# GPSLoRaNode_Schematic.net
KiCad netlist of a schematic drawn in Altium Designer
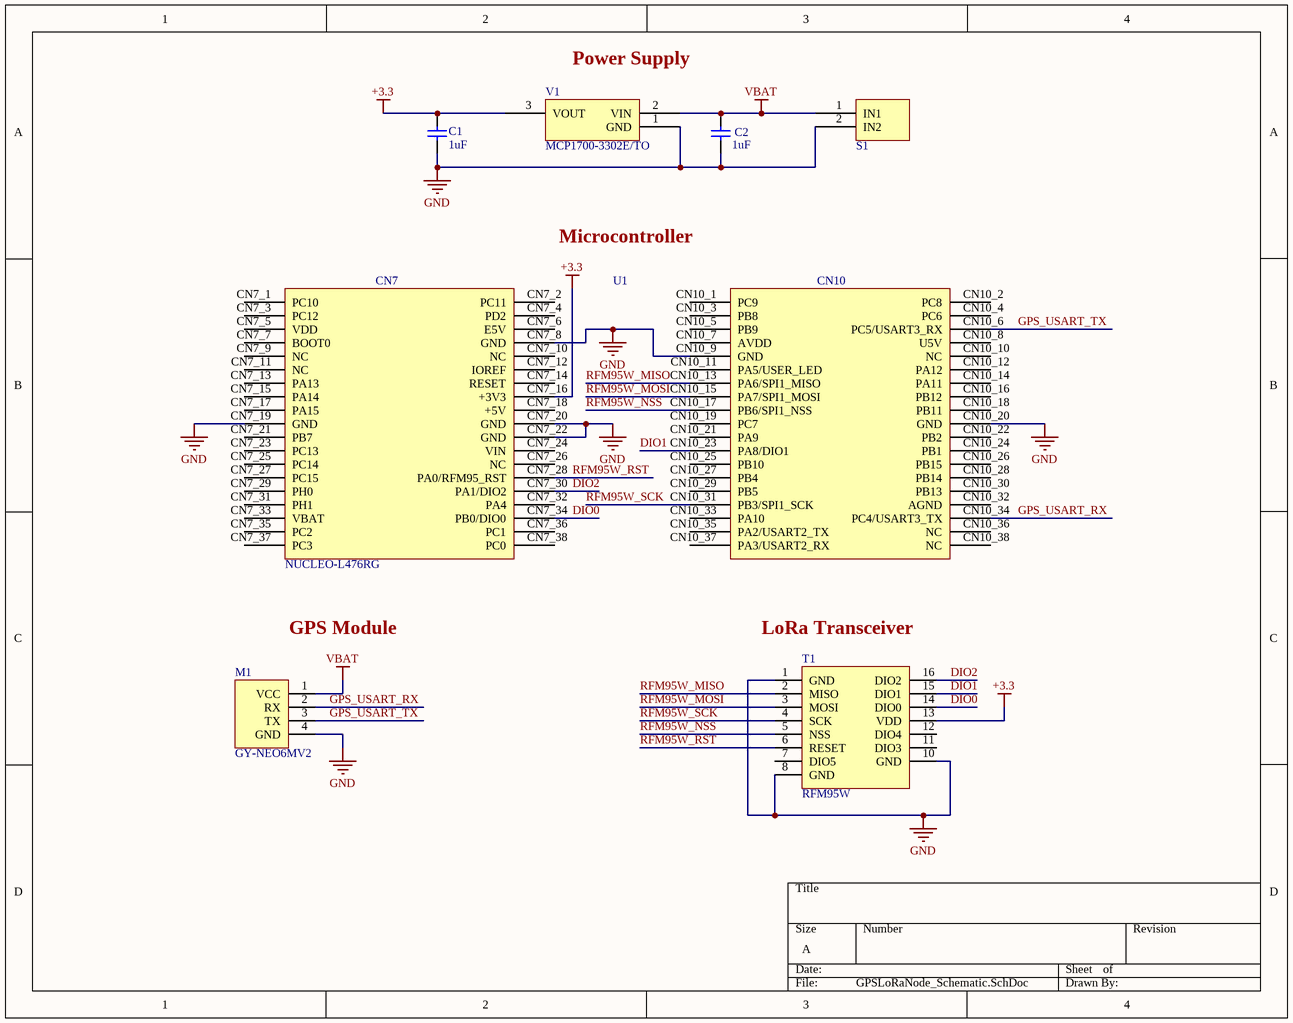
[diagram p0: GPSLoRaNode_Schematic.SchDoc]

(export (version "E")
  (design (tool "Eeschema 10.0.6"))
  (components
    (comp (ref "C1")
      (value "1uF")
      (footprint "C1uFTantalum")
      (description "CAP TANT 1UF 10% 35V RADIAL")
      (fields
        (field (name "MANUFACTURER") "KEMET")
        (field (name "MANUFACTURER PART NUMBER") "T350A105K035AS7301")
      )
      (libsource (lib "GPSLoRaNode") (part "T350A105K035AS7301"))
    )
    (comp (ref "C2")
      (value "1uF")
      (footprint "C1uFTantalum")
      (description "CAP TANT 1UF 10% 35V RADIAL")
      (fields
        (field (name "MANUFACTURER") "KEMET")
        (field (name "MANUFACTURER PART NUMBER") "T350A105K035AS7301")
      )
      (libsource (lib "GPSLoRaNode") (part "T350A105K035AS7301"))
    )
    (comp (ref "M1") (value "GY-NEO6MV2") (libsource (lib "GPSLoRaNode") (part "GY-NEO6MV2")))
    (comp (ref "S1")
      (value "2PositionScrewTerminal")
      (footprint "2POSITIONSCREWTERMINAL")
      (fields
        (field (name "MANUFACTURER") "Phoenix Contact")
        (field (name "MANUFACTURER PART NUMBER") "1725656")
        (field (name "VOLTAGE") "125V")
      )
      (libsource (lib "GPSLoRaNode") (part "2PositionScrewTerminal"))
    )
    (comp (ref "T1")
      (value "RFM95W")
      (footprint "HDR1X8")
      (description "RFM95W Breakout Board")
      (fields (field (name "MANUFACTURER") "Molex") (field (name "MANUFACTURER PART NUMBER") "22-10-2061"))
      (libsource (lib "GPSLoRaNode") (part "RFM95W"))
    )
    (comp (ref "U1")
      (value "NUCLEO-L476RG")
      (footprint "NUCLEOL476RG")
      (description "16/32-BITS MICROS")
      (fields (field (name "MANUFACTURER") "STMicroelectronics"))
      (libsource (lib "GPSLoRaNode") (part "NUCLEO-L476RG"))
    )
    (comp (ref "V1")
      (value "MCP1700-3302E/TO")
      (footprint "MCP1700")
      (description "LDO Regulator Pos 3.3V 0.25A 3-Pin TO-92 Bag")
      (fields (field (name "MANUFACTURER") "Microchip"))
      (libsource (lib "GPSLoRaNode") (part "MCP1700-3302E/TO"))
    )
  )
  (nets
    (net (code "1") (name "+3.3") (class "Default")
      (node (ref "C1") (pin "2") (pinfunction "2_2") (pintype "passive"))
      (node (ref "T1") (pin "13") (pinfunction "VDD_13") (pintype "passive"))
      (node (ref "U1") (pin "CN7_16") (pinfunction "+3V3_CN7_16") (pintype "passive"))
      (node (ref "V1") (pin "3") (pinfunction "VOUT_3") (pintype "passive"))
    )
    (net (code "2") (name "/DIO0") (class "Default")
      (node (ref "T1") (pin "14") (pinfunction "DIO0_14") (pintype "passive"))
      (node (ref "U1") (pin "CN7_34") (pinfunction "PB0/DIO0_CN7_34") (pintype "passive"))
    )
    (net (code "3") (name "/DIO1") (class "Default")
      (node (ref "T1") (pin "15") (pinfunction "DIO1_15") (pintype "passive"))
      (node (ref "U1") (pin "CN10_23") (pinfunction "PA8/DIO1_CN10_23") (pintype "passive"))
    )
    (net (code "4") (name "/DIO2") (class "Default")
      (node (ref "T1") (pin "16") (pinfunction "DIO2_16") (pintype "passive"))
      (node (ref "U1") (pin "CN7_30") (pinfunction "PA1/DIO2_CN7_30") (pintype "passive"))
    )
    (net (code "5") (name "/GPS_USART_RX") (class "Default")
      (node (ref "M1") (pin "2") (pinfunction "RX_2") (pintype "passive"))
      (node (ref "U1") (pin "CN10_34") (pinfunction "PC4/USART3_TX_CN10_34") (pintype "passive"))
    )
    (net (code "6") (name "/GPS_USART_TX") (class "Default")
      (node (ref "M1") (pin "3") (pinfunction "TX_3") (pintype "passive"))
      (node (ref "U1") (pin "CN10_6") (pinfunction "PC5/USART3_RX_CN10_6") (pintype "passive"))
    )
    (net (code "7") (name "/RFM95W_MISO") (class "Default")
      (node (ref "T1") (pin "2") (pinfunction "MISO_2") (pintype "passive"))
      (node (ref "U1") (pin "CN10_13") (pinfunction "PA6/SPI1_MISO_CN10_13") (pintype "passive"))
    )
    (net (code "8") (name "/RFM95W_MOSI") (class "Default")
      (node (ref "T1") (pin "3") (pinfunction "MOSI_3") (pintype "passive"))
      (node (ref "U1") (pin "CN10_15") (pinfunction "PA7/SPI1_MOSI_CN10_15") (pintype "passive"))
    )
    (net (code "9") (name "/RFM95W_NSS") (class "Default")
      (node (ref "T1") (pin "5") (pinfunction "NSS_5") (pintype "passive"))
      (node (ref "U1") (pin "CN10_17") (pinfunction "PB6/SPI1_NSS_CN10_17") (pintype "passive"))
    )
    (net (code "10") (name "/RFM95W_RST") (class "Default")
      (node (ref "T1") (pin "6") (pinfunction "RESET_6") (pintype "passive"))
      (node (ref "U1") (pin "CN7_28") (pinfunction "PA0/RFM95_RST_CN7_28") (pintype "passive"))
    )
    (net (code "11") (name "/RFM95W_SCK") (class "Default")
      (node (ref "T1") (pin "4") (pinfunction "SCK_4") (pintype "passive"))
      (node (ref "U1") (pin "CN10_31") (pinfunction "PB3/SPI1_SCK_CN10_31") (pintype "passive"))
    )
    (net (code "12") (name "GND") (class "Default")
      (node (ref "C1") (pin "1") (pinfunction "1_1") (pintype "passive"))
      (node (ref "C2") (pin "1") (pinfunction "1_1") (pintype "passive"))
      (node (ref "M1") (pin "4") (pinfunction "GND_4") (pintype "passive"))
      (node (ref "S1") (pin "2") (pinfunction "IN2_2") (pintype "passive"))
      (node (ref "T1") (pin "1") (pinfunction "GND_1") (pintype "passive"))
      (node (ref "T1") (pin "10") (pinfunction "GND_10") (pintype "passive"))
      (node (ref "T1") (pin "8") (pinfunction "GND_8") (pintype "passive"))
      (node (ref "U1") (pin "CN10_20") (pinfunction "GND_CN10_20") (pintype "passive"))
      (node (ref "U1") (pin "CN10_9") (pinfunction "GND_CN10_9") (pintype "passive"))
      (node (ref "U1") (pin "CN7_19") (pinfunction "GND_CN7_19") (pintype "passive"))
      (node (ref "U1") (pin "CN7_20") (pinfunction "GND_CN7_20") (pintype "passive"))
      (node (ref "U1") (pin "CN7_22") (pinfunction "GND_CN7_22") (pintype "passive"))
      (node (ref "U1") (pin "CN7_8") (pinfunction "GND_CN7_8") (pintype "passive"))
      (node (ref "V1") (pin "1") (pinfunction "GND_1") (pintype "passive"))
    )
    (net (code "13") (name "VBAT") (class "Default")
      (node (ref "C2") (pin "2") (pinfunction "2_2") (pintype "passive"))
      (node (ref "M1") (pin "1") (pinfunction "VCC_1") (pintype "passive"))
      (node (ref "S1") (pin "1") (pinfunction "IN1_1") (pintype "passive"))
      (node (ref "V1") (pin "2") (pinfunction "VIN_2") (pintype "passive"))
    )
    (net (code "14") (name "unconnected-(T1-DIO3-Pad11)") (class "Default")
      (node (ref "T1") (pin "11") (pinfunction "DIO3_11") (pintype "passive"))
    )
    (net (code "15") (name "unconnected-(T1-DIO4-Pad12)") (class "Default")
      (node (ref "T1") (pin "12") (pinfunction "DIO4_12") (pintype "passive"))
    )
    (net (code "16") (name "unconnected-(T1-DIO5-Pad7)") (class "Default")
      (node (ref "T1") (pin "7") (pinfunction "DIO5_7") (pintype "passive"))
    )
    (net (code "17") (name "unconnected-(U1-+5V-PadCN7_18)") (class "Default")
      (node (ref "U1") (pin "CN7_18") (pinfunction "+5V_CN7_18") (pintype "passive"))
    )
    (net (code "18") (name "unconnected-(U1-AGND-PadCN10_32)") (class "Default")
      (node (ref "U1") (pin "CN10_32") (pinfunction "AGND_CN10_32") (pintype "passive"))
    )
    (net (code "19") (name "unconnected-(U1-AVDD-PadCN10_7)") (class "Default")
      (node (ref "U1") (pin "CN10_7") (pinfunction "AVDD_CN10_7") (pintype "passive"))
    )
    (net (code "20") (name "unconnected-(U1-BOOT0-PadCN7_7)") (class "Default")
      (node (ref "U1") (pin "CN7_7") (pinfunction "BOOT0_CN7_7") (pintype "passive"))
    )
    (net (code "21") (name "unconnected-(U1-E5V-PadCN7_6)") (class "Default")
      (node (ref "U1") (pin "CN7_6") (pinfunction "E5V_CN7_6") (pintype "passive"))
    )
    (net (code "22") (name "unconnected-(U1-IOREF-PadCN7_12)") (class "Default")
      (node (ref "U1") (pin "CN7_12") (pinfunction "IOREF_CN7_12") (pintype "passive"))
    )
    (net (code "23") (name "unconnected-(U1-NC-PadCN7_9)") (class "Default")
      (node (ref "U1") (pin "CN7_9") (pinfunction "NC_CN7_9") (pintype "passive"))
    )
    (net (code "24") (name "unconnected-(U1-NC-PadCN7_10)") (class "Default")
      (node (ref "U1") (pin "CN7_10") (pinfunction "NC_CN7_10") (pintype "passive"))
    )
    (net (code "25") (name "unconnected-(U1-NC-PadCN7_11)") (class "Default")
      (node (ref "U1") (pin "CN7_11") (pinfunction "NC_CN7_11") (pintype "passive"))
    )
    (net (code "26") (name "unconnected-(U1-NC-PadCN7_26)") (class "Default")
      (node (ref "U1") (pin "CN7_26") (pinfunction "NC_CN7_26") (pintype "passive"))
    )
    (net (code "27") (name "unconnected-(U1-NC-PadCN10_10)") (class "Default")
      (node (ref "U1") (pin "CN10_10") (pinfunction "NC_CN10_10") (pintype "passive"))
    )
    (net (code "28") (name "unconnected-(U1-NC-PadCN10_36)") (class "Default")
      (node (ref "U1") (pin "CN10_36") (pinfunction "NC_CN10_36") (pintype "passive"))
    )
    (net (code "29") (name "unconnected-(U1-NC-PadCN10_38)") (class "Default")
      (node (ref "U1") (pin "CN10_38") (pinfunction "NC_CN10_38") (pintype "passive"))
    )
    (net (code "30") (name "unconnected-(U1-PA2{slash}USART2_TX-PadCN10_35)") (class "Default")
      (node (ref "U1") (pin "CN10_35") (pinfunction "PA2/USART2_TX_CN10_35") (pintype "passive"))
    )
    (net (code "31") (name "unconnected-(U1-PA3{slash}USART2_RX-PadCN10_37)") (class "Default")
      (node (ref "U1") (pin "CN10_37") (pinfunction "PA3/USART2_RX_CN10_37") (pintype "passive"))
    )
    (net (code "32") (name "unconnected-(U1-PA4-PadCN7_32)") (class "Default")
      (node (ref "U1") (pin "CN7_32") (pinfunction "PA4_CN7_32") (pintype "passive"))
    )
    (net (code "33") (name "unconnected-(U1-PA5{slash}USER_LED-PadCN10_11)") (class "Default")
      (node (ref "U1") (pin "CN10_11") (pinfunction "PA5/USER_LED_CN10_11") (pintype "passive"))
    )
    (net (code "34") (name "unconnected-(U1-PA9-PadCN10_21)") (class "Default")
      (node (ref "U1") (pin "CN10_21") (pinfunction "PA9_CN10_21") (pintype "passive"))
    )
    (net (code "35") (name "unconnected-(U1-PA10-PadCN10_33)") (class "Default")
      (node (ref "U1") (pin "CN10_33") (pinfunction "PA10_CN10_33") (pintype "passive"))
    )
    (net (code "36") (name "unconnected-(U1-PA11-PadCN10_14)") (class "Default")
      (node (ref "U1") (pin "CN10_14") (pinfunction "PA11_CN10_14") (pintype "passive"))
    )
    (net (code "37") (name "unconnected-(U1-PA12-PadCN10_12)") (class "Default")
      (node (ref "U1") (pin "CN10_12") (pinfunction "PA12_CN10_12") (pintype "passive"))
    )
    (net (code "38") (name "unconnected-(U1-PA13-PadCN7_13)") (class "Default")
      (node (ref "U1") (pin "CN7_13") (pinfunction "PA13_CN7_13") (pintype "passive"))
    )
    (net (code "39") (name "unconnected-(U1-PA14-PadCN7_15)") (class "Default")
      (node (ref "U1") (pin "CN7_15") (pinfunction "PA14_CN7_15") (pintype "passive"))
    )
    (net (code "40") (name "unconnected-(U1-PA15-PadCN7_17)") (class "Default")
      (node (ref "U1") (pin "CN7_17") (pinfunction "PA15_CN7_17") (pintype "passive"))
    )
    (net (code "41") (name "unconnected-(U1-PB1-PadCN10_24)") (class "Default")
      (node (ref "U1") (pin "CN10_24") (pinfunction "PB1_CN10_24") (pintype "passive"))
    )
    (net (code "42") (name "unconnected-(U1-PB2-PadCN10_22)") (class "Default")
      (node (ref "U1") (pin "CN10_22") (pinfunction "PB2_CN10_22") (pintype "passive"))
    )
    (net (code "43") (name "unconnected-(U1-PB4-PadCN10_27)") (class "Default")
      (node (ref "U1") (pin "CN10_27") (pinfunction "PB4_CN10_27") (pintype "passive"))
    )
    (net (code "44") (name "unconnected-(U1-PB5-PadCN10_29)") (class "Default")
      (node (ref "U1") (pin "CN10_29") (pinfunction "PB5_CN10_29") (pintype "passive"))
    )
    (net (code "45") (name "unconnected-(U1-PB7-PadCN7_21)") (class "Default")
      (node (ref "U1") (pin "CN7_21") (pinfunction "PB7_CN7_21") (pintype "passive"))
    )
    (net (code "46") (name "unconnected-(U1-PB8-PadCN10_3)") (class "Default")
      (node (ref "U1") (pin "CN10_3") (pinfunction "PB8_CN10_3") (pintype "passive"))
    )
    (net (code "47") (name "unconnected-(U1-PB9-PadCN10_5)") (class "Default")
      (node (ref "U1") (pin "CN10_5") (pinfunction "PB9_CN10_5") (pintype "passive"))
    )
    (net (code "48") (name "unconnected-(U1-PB10-PadCN10_25)") (class "Default")
      (node (ref "U1") (pin "CN10_25") (pinfunction "PB10_CN10_25") (pintype "passive"))
    )
    (net (code "49") (name "unconnected-(U1-PB11-PadCN10_18)") (class "Default")
      (node (ref "U1") (pin "CN10_18") (pinfunction "PB11_CN10_18") (pintype "passive"))
    )
    (net (code "50") (name "unconnected-(U1-PB12-PadCN10_16)") (class "Default")
      (node (ref "U1") (pin "CN10_16") (pinfunction "PB12_CN10_16") (pintype "passive"))
    )
    (net (code "51") (name "unconnected-(U1-PB13-PadCN10_30)") (class "Default")
      (node (ref "U1") (pin "CN10_30") (pinfunction "PB13_CN10_30") (pintype "passive"))
    )
    (net (code "52") (name "unconnected-(U1-PB14-PadCN10_28)") (class "Default")
      (node (ref "U1") (pin "CN10_28") (pinfunction "PB14_CN10_28") (pintype "passive"))
    )
    (net (code "53") (name "unconnected-(U1-PB15-PadCN10_26)") (class "Default")
      (node (ref "U1") (pin "CN10_26") (pinfunction "PB15_CN10_26") (pintype "passive"))
    )
    (net (code "54") (name "unconnected-(U1-PC0-PadCN7_38)") (class "Default")
      (node (ref "U1") (pin "CN7_38") (pinfunction "PC0_CN7_38") (pintype "passive"))
    )
    (net (code "55") (name "unconnected-(U1-PC1-PadCN7_36)") (class "Default")
      (node (ref "U1") (pin "CN7_36") (pinfunction "PC1_CN7_36") (pintype "passive"))
    )
    (net (code "56") (name "unconnected-(U1-PC2-PadCN7_35)") (class "Default")
      (node (ref "U1") (pin "CN7_35") (pinfunction "PC2_CN7_35") (pintype "passive"))
    )
    (net (code "57") (name "unconnected-(U1-PC3-PadCN7_37)") (class "Default")
      (node (ref "U1") (pin "CN7_37") (pinfunction "PC3_CN7_37") (pintype "passive"))
    )
    (net (code "58") (name "unconnected-(U1-PC6-PadCN10_4)") (class "Default")
      (node (ref "U1") (pin "CN10_4") (pinfunction "PC6_CN10_4") (pintype "passive"))
    )
    (net (code "59") (name "unconnected-(U1-PC7-PadCN10_19)") (class "Default")
      (node (ref "U1") (pin "CN10_19") (pinfunction "PC7_CN10_19") (pintype "passive"))
    )
    (net (code "60") (name "unconnected-(U1-PC8-PadCN10_2)") (class "Default")
      (node (ref "U1") (pin "CN10_2") (pinfunction "PC8_CN10_2") (pintype "passive"))
    )
    (net (code "61") (name "unconnected-(U1-PC9-PadCN10_1)") (class "Default")
      (node (ref "U1") (pin "CN10_1") (pinfunction "PC9_CN10_1") (pintype "passive"))
    )
    (net (code "62") (name "unconnected-(U1-PC10-PadCN7_1)") (class "Default")
      (node (ref "U1") (pin "CN7_1") (pinfunction "PC10_CN7_1") (pintype "passive"))
    )
    (net (code "63") (name "unconnected-(U1-PC11-PadCN7_2)") (class "Default")
      (node (ref "U1") (pin "CN7_2") (pinfunction "PC11_CN7_2") (pintype "passive"))
    )
    (net (code "64") (name "unconnected-(U1-PC12-PadCN7_3)") (class "Default")
      (node (ref "U1") (pin "CN7_3") (pinfunction "PC12_CN7_3") (pintype "passive"))
    )
    (net (code "65") (name "unconnected-(U1-PC13-PadCN7_23)") (class "Default")
      (node (ref "U1") (pin "CN7_23") (pinfunction "PC13_CN7_23") (pintype "passive"))
    )
    (net (code "66") (name "unconnected-(U1-PC14-PadCN7_25)") (class "Default")
      (node (ref "U1") (pin "CN7_25") (pinfunction "PC14_CN7_25") (pintype "passive"))
    )
    (net (code "67") (name "unconnected-(U1-PC15-PadCN7_27)") (class "Default")
      (node (ref "U1") (pin "CN7_27") (pinfunction "PC15_CN7_27") (pintype "passive"))
    )
    (net (code "68") (name "unconnected-(U1-PD2-PadCN7_4)") (class "Default")
      (node (ref "U1") (pin "CN7_4") (pinfunction "PD2_CN7_4") (pintype "passive"))
    )
    (net (code "69") (name "unconnected-(U1-PH0-PadCN7_29)") (class "Default")
      (node (ref "U1") (pin "CN7_29") (pinfunction "PH0_CN7_29") (pintype "passive"))
    )
    (net (code "70") (name "unconnected-(U1-PH1-PadCN7_31)") (class "Default")
      (node (ref "U1") (pin "CN7_31") (pinfunction "PH1_CN7_31") (pintype "passive"))
    )
    (net (code "71") (name "unconnected-(U1-RESET-PadCN7_14)") (class "Default")
      (node (ref "U1") (pin "CN7_14") (pinfunction "RESET_CN7_14") (pintype "passive"))
    )
    (net (code "72") (name "unconnected-(U1-U5V-PadCN10_8)") (class "Default")
      (node (ref "U1") (pin "CN10_8") (pinfunction "U5V_CN10_8") (pintype "passive"))
    )
    (net (code "73") (name "unconnected-(U1-VBAT-PadCN7_33)") (class "Default")
      (node (ref "U1") (pin "CN7_33") (pinfunction "VBAT_CN7_33") (pintype "passive"))
    )
    (net (code "74") (name "unconnected-(U1-VDD-PadCN7_5)") (class "Default")
      (node (ref "U1") (pin "CN7_5") (pinfunction "VDD_CN7_5") (pintype "passive"))
    )
    (net (code "75") (name "unconnected-(U1-VIN-PadCN7_24)") (class "Default")
      (node (ref "U1") (pin "CN7_24") (pinfunction "VIN_CN7_24") (pintype "passive"))
    )
  )
)
